# LinefollowerAmateur.net
KiCad netlist of a schematic drawn in EasyEDA
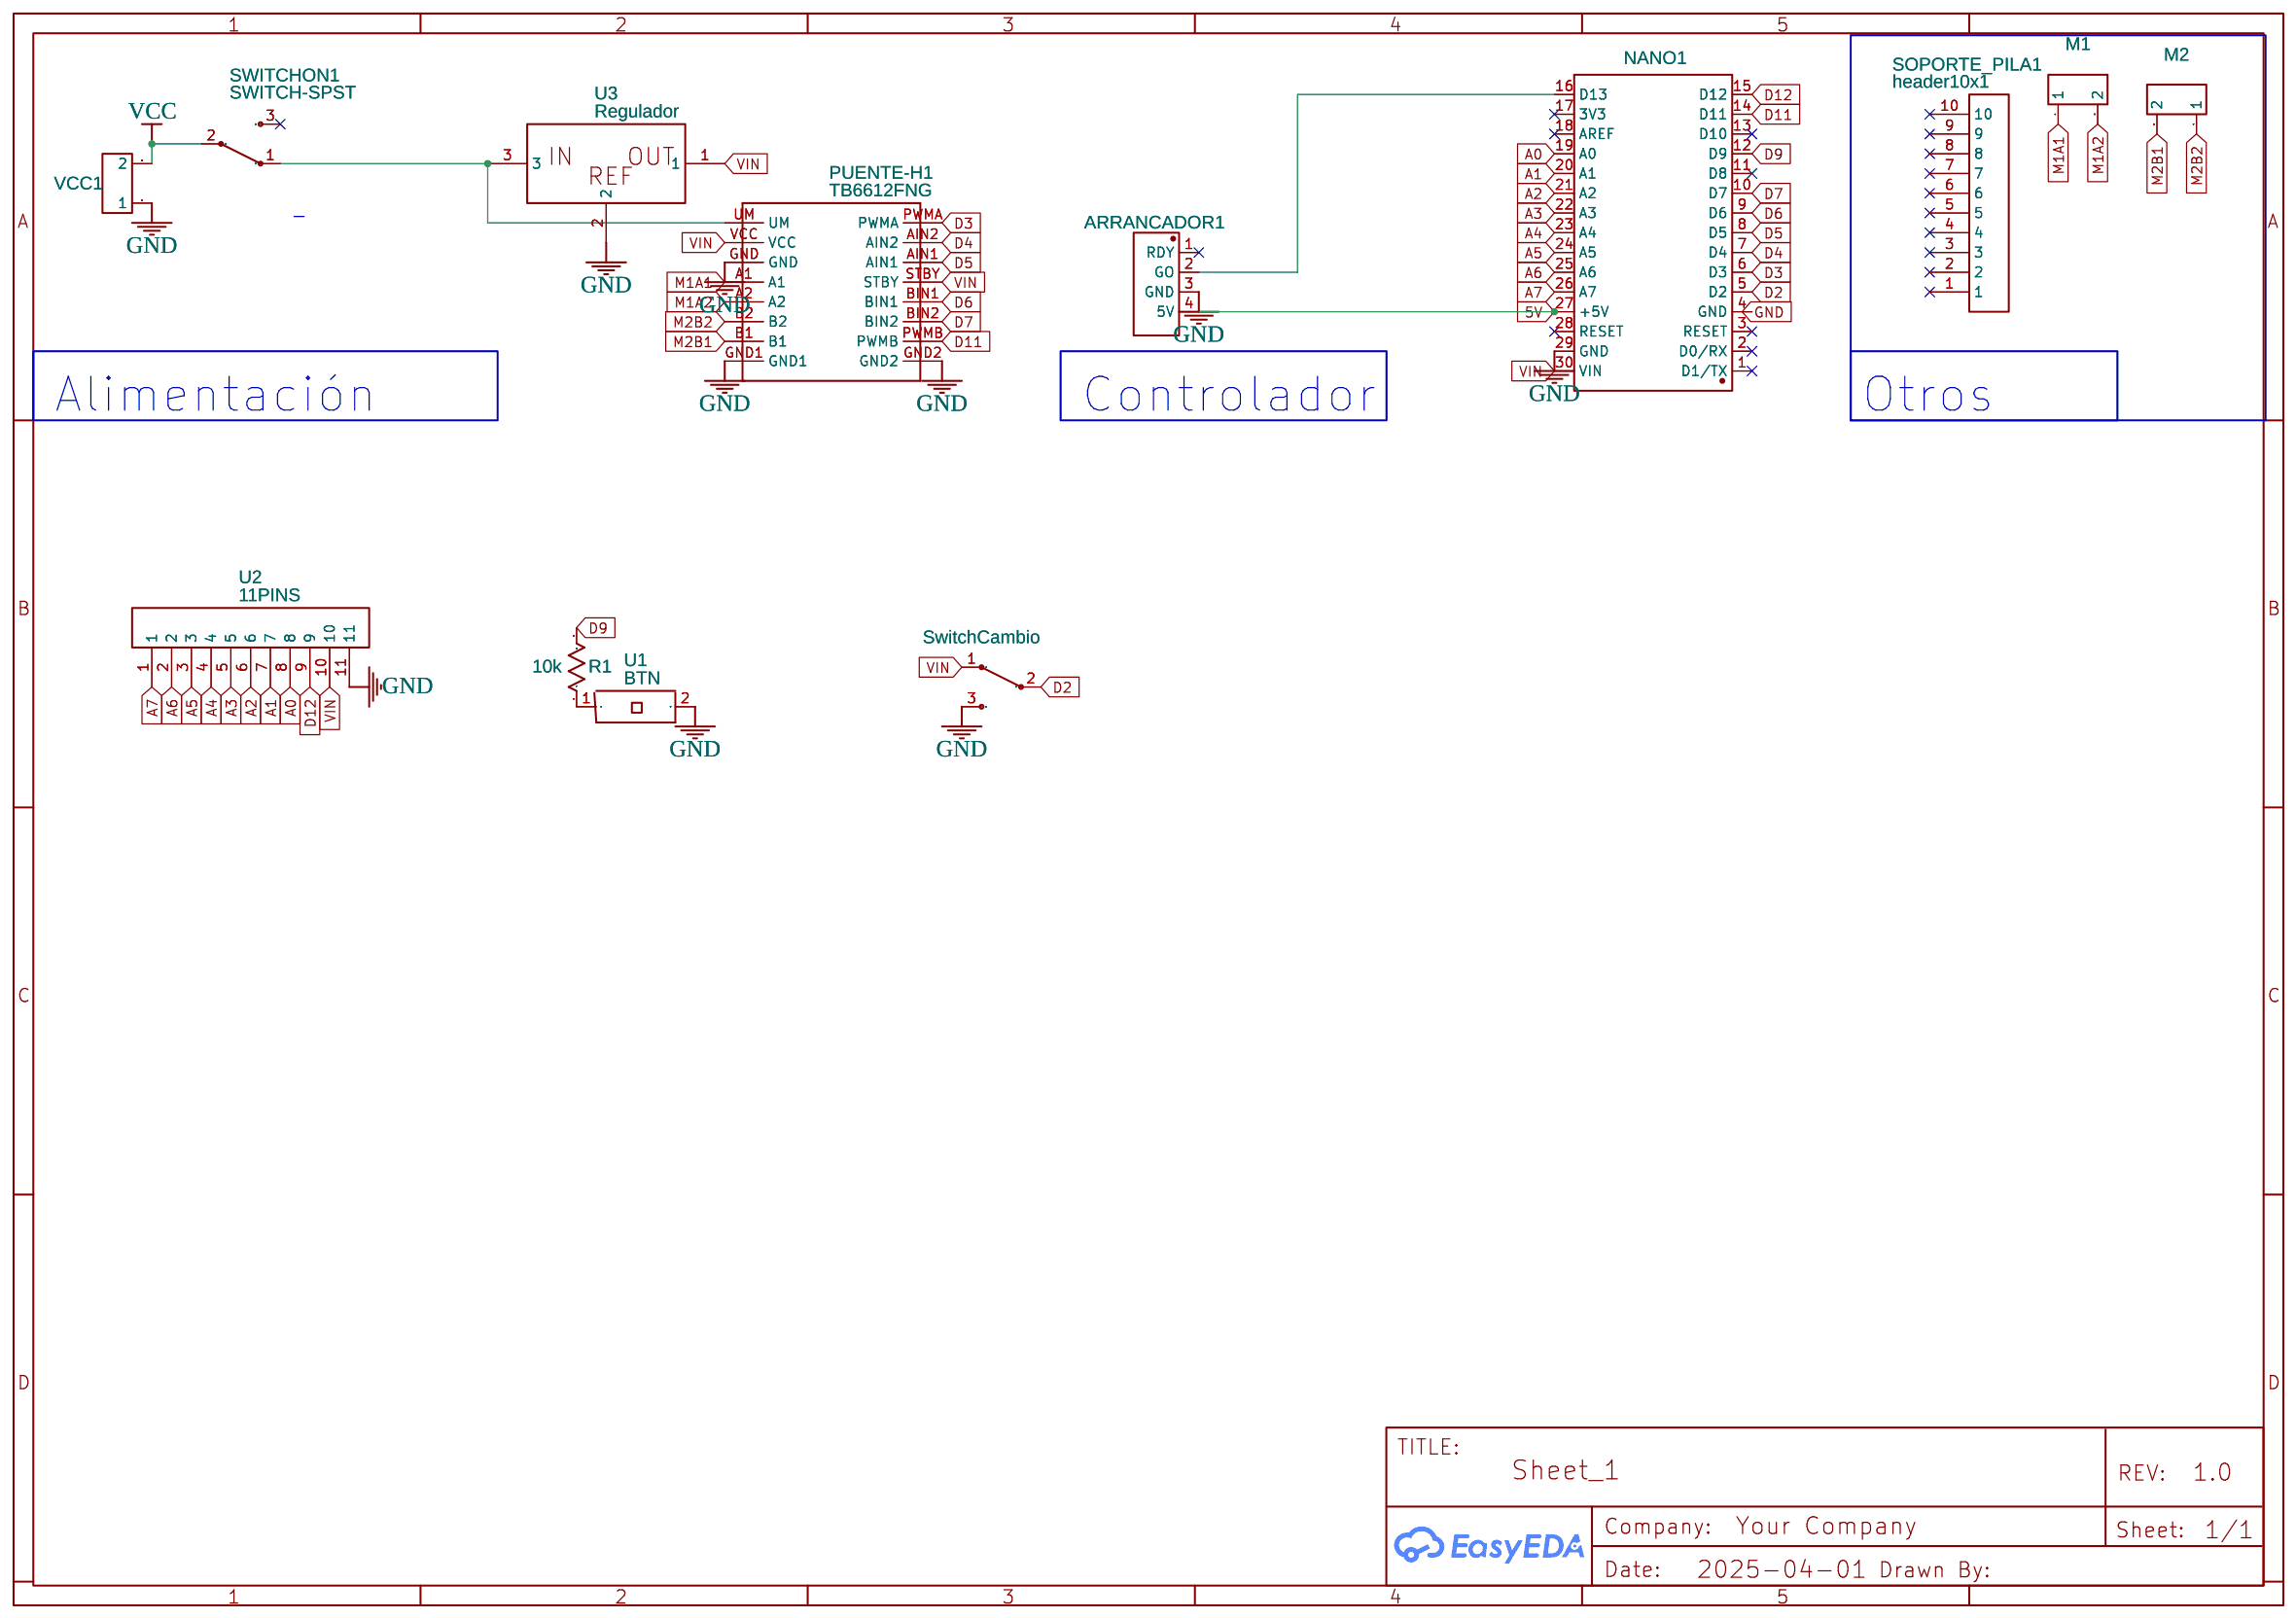
[diagram p0: schematic sheet]

(export (version "E")
  (design (tool "Eeschema 10.0.6"))
  (components
    (comp (ref "ARRANCADOR1") (value "HEADER 1X4P COPY") (libsource (lib "") (part "HEADER 1X4P COPY")))
    (comp (ref "M1")
      (value "CONNECTOR 2 PINS")
      (fields
        (field (name "Manufacturer Part") "Female headerHDR1X8-2.54")
        (field (name "Manufacturer") "BOOMELE")
      )
      (libsource (lib "") (part "HEADER PAD 2X"))
    )
    (comp (ref "M2")
      (value "CONNECTOR 2 PINS")
      (fields
        (field (name "Manufacturer Part") "Female headerHDR1X8-2.54")
        (field (name "Manufacturer") "BOOMELE")
      )
      (libsource (lib "") (part "HEADER PAD 2X_1"))
    )
    (comp (ref "NANO1") (value "ARDUINO_NANO") (libsource (lib "") (part "ARDUINO_NANO")))
    (comp (ref "PUENTE-H1") (value "TB6612FNG") (libsource (lib "") (part "TB6612FNG")))
    (comp (ref "R1")
      (value "10k")
      (fields (field (name "Manufacturer Part") "RESISTOR_ALONG") (field (name "Manufacturer") "MULTICOMP"))
      (libsource (lib "") (part "10k"))
    )
    (comp (ref "SOPORTE_PILA1") (value "header10x1") (libsource (lib "") (part "header10x1")))
    (comp (ref "SWITCHCAMBIO1") (value "SwitchCambio") (libsource (lib "") (part "SWITCH-SPST")))
    (comp (ref "SWITCHON1") (value "SWITCH-SPST") (libsource (lib "") (part "SWITCH-SPST_1")))
    (comp (ref "U1") (value "BTN") (libsource (lib "") (part "BTN")))
    (comp (ref "U2") (value "11PINS") (libsource (lib "") (part "11PINS")))
    (comp (ref "U3") (value "Regulador") (libsource (lib "") (part "Regulador")))
    (comp (ref "VCC1")
      (value "CONNECTOR 2 PINS")
      (fields
        (field (name "Manufacturer Part") "Female headerHDR1X8-2.54")
        (field (name "Manufacturer") "BOOMELE")
      )
      (libsource (lib "") (part "HEADER PAD 2X_2"))
    )
  )
  (nets
    (net (code "1") (name "5V") (class "Default")
      (node (ref "ARRANCADOR1") (pin "4") (pinfunction "5V_4") (pintype "unspecified"))
      (node (ref "NANO1") (pin "27") (pinfunction "+5V_27") (pintype "unspecified"))
    )
    (net (code "2") (name "A0") (class "Default")
      (node (ref "NANO1") (pin "19") (pinfunction "A0_19") (pintype "unspecified"))
      (node (ref "U2") (pin "8") (pinfunction "8_8") (pintype "unspecified"))
    )
    (net (code "3") (name "A1") (class "Default")
      (node (ref "NANO1") (pin "20") (pinfunction "A1_20") (pintype "unspecified"))
      (node (ref "U2") (pin "7") (pinfunction "7_7") (pintype "unspecified"))
    )
    (net (code "4") (name "A2") (class "Default")
      (node (ref "NANO1") (pin "21") (pinfunction "A2_21") (pintype "unspecified"))
      (node (ref "U2") (pin "6") (pinfunction "6_6") (pintype "unspecified"))
    )
    (net (code "5") (name "A3") (class "Default")
      (node (ref "NANO1") (pin "22") (pinfunction "A3_22") (pintype "unspecified"))
      (node (ref "U2") (pin "5") (pinfunction "5_5") (pintype "unspecified"))
    )
    (net (code "6") (name "A4") (class "Default")
      (node (ref "NANO1") (pin "23") (pinfunction "A4_23") (pintype "unspecified"))
      (node (ref "U2") (pin "4") (pinfunction "4_4") (pintype "unspecified"))
    )
    (net (code "7") (name "A5") (class "Default")
      (node (ref "NANO1") (pin "24") (pinfunction "A5_24") (pintype "unspecified"))
      (node (ref "U2") (pin "3") (pinfunction "3_3") (pintype "unspecified"))
    )
    (net (code "8") (name "A6") (class "Default")
      (node (ref "NANO1") (pin "25") (pinfunction "A6_25") (pintype "unspecified"))
      (node (ref "U2") (pin "2") (pinfunction "2_2") (pintype "unspecified"))
    )
    (net (code "9") (name "A7") (class "Default")
      (node (ref "NANO1") (pin "26") (pinfunction "A7_26") (pintype "unspecified"))
      (node (ref "U2") (pin "1") (pinfunction "1_1") (pintype "unspecified"))
    )
    (net (code "10") (name "D2") (class "Default")
      (node (ref "NANO1") (pin "5") (pinfunction "D2_5") (pintype "unspecified"))
      (node (ref "SWITCHCAMBIO1") (pin "2") (pinfunction "2_2") (pintype "unspecified"))
    )
    (net (code "11") (name "D3") (class "Default")
      (node (ref "NANO1") (pin "6") (pinfunction "D3_6") (pintype "unspecified"))
      (node (ref "PUENTE-H1") (pin "PWMA") (pinfunction "PWMA_PWMA") (pintype "bidirectional"))
    )
    (net (code "12") (name "D4") (class "Default")
      (node (ref "NANO1") (pin "7") (pinfunction "D4_7") (pintype "unspecified"))
      (node (ref "PUENTE-H1") (pin "AIN2") (pinfunction "AIN2_AIN2") (pintype "bidirectional"))
    )
    (net (code "13") (name "D5") (class "Default")
      (node (ref "NANO1") (pin "8") (pinfunction "D5_8") (pintype "unspecified"))
      (node (ref "PUENTE-H1") (pin "AIN1") (pinfunction "AIN1_AIN1") (pintype "bidirectional"))
    )
    (net (code "14") (name "D6") (class "Default")
      (node (ref "NANO1") (pin "9") (pinfunction "D6_9") (pintype "unspecified"))
      (node (ref "PUENTE-H1") (pin "BIN1") (pinfunction "BIN1_BIN1") (pintype "bidirectional"))
    )
    (net (code "15") (name "D7") (class "Default")
      (node (ref "NANO1") (pin "10") (pinfunction "D7_10") (pintype "unspecified"))
      (node (ref "PUENTE-H1") (pin "BIN2") (pinfunction "BIN2_BIN2") (pintype "bidirectional"))
    )
    (net (code "16") (name "D9") (class "Default")
      (node (ref "NANO1") (pin "12") (pinfunction "D9_12") (pintype "unspecified"))
      (node (ref "R1") (pin "2") (pinfunction "2_2") (pintype "unspecified"))
    )
    (net (code "17") (name "D11") (class "Default")
      (node (ref "NANO1") (pin "14") (pinfunction "D11_14") (pintype "unspecified"))
      (node (ref "PUENTE-H1") (pin "PWMB") (pinfunction "PWMB_PWMB") (pintype "bidirectional"))
    )
    (net (code "18") (name "D12") (class "Default")
      (node (ref "NANO1") (pin "15") (pinfunction "D12_15") (pintype "unspecified"))
      (node (ref "U2") (pin "9") (pinfunction "9_9") (pintype "unspecified"))
    )
    (net (code "19") (name "GND") (class "Default")
      (node (ref "ARRANCADOR1") (pin "3") (pinfunction "GND_3") (pintype "unspecified"))
      (node (ref "NANO1") (pin "29") (pinfunction "GND_29") (pintype "unspecified"))
      (node (ref "NANO1") (pin "4") (pinfunction "GND_4") (pintype "unspecified"))
      (node (ref "PUENTE-H1") (pin "GND") (pinfunction "GND_GND") (pintype "bidirectional"))
      (node (ref "PUENTE-H1") (pin "GND1") (pinfunction "GND1_GND1") (pintype "bidirectional"))
      (node (ref "PUENTE-H1") (pin "GND2") (pinfunction "GND2_GND2") (pintype "bidirectional"))
      (node (ref "SWITCHCAMBIO1") (pin "3") (pinfunction "3_3") (pintype "unspecified"))
      (node (ref "U1") (pin "2") (pinfunction "2_2") (pintype "unspecified"))
      (node (ref "U2") (pin "11") (pinfunction "11_11") (pintype "unspecified"))
      (node (ref "U3") (pin "2") (pinfunction "2_2") (pintype "unspecified"))
      (node (ref "VCC1") (pin "1") (pinfunction "1_1") (pintype "unspecified"))
    )
    (net (code "20") (name "M1A1") (class "Default")
      (node (ref "M1") (pin "1") (pinfunction "1_1") (pintype "unspecified"))
      (node (ref "PUENTE-H1") (pin "A1") (pinfunction "A1_A1") (pintype "bidirectional"))
    )
    (net (code "21") (name "M1A2") (class "Default")
      (node (ref "M1") (pin "2") (pinfunction "2_2") (pintype "unspecified"))
      (node (ref "PUENTE-H1") (pin "A2") (pinfunction "A2_A2") (pintype "bidirectional"))
    )
    (net (code "22") (name "M2B1") (class "Default")
      (node (ref "M2") (pin "2") (pinfunction "2_2") (pintype "unspecified"))
      (node (ref "PUENTE-H1") (pin "B1") (pinfunction "B1_B1") (pintype "bidirectional"))
    )
    (net (code "23") (name "M2B2") (class "Default")
      (node (ref "M2") (pin "1") (pinfunction "1_1") (pintype "unspecified"))
      (node (ref "PUENTE-H1") (pin "B2") (pinfunction "B2_B2") (pintype "bidirectional"))
    )
    (net (code "24") (name "Net-(ARRANCADOR1-GO)") (class "Default")
      (node (ref "ARRANCADOR1") (pin "2") (pinfunction "GO_2") (pintype "unspecified"))
      (node (ref "NANO1") (pin "16") (pinfunction "D13_16") (pintype "unspecified"))
    )
    (net (code "25") (name "Net-(PUENTE-H1-PadUM)") (class "Default")
      (node (ref "PUENTE-H1") (pin "UM") (pinfunction "UM_UM") (pintype "bidirectional"))
      (node (ref "SWITCHON1") (pin "1") (pinfunction "1_1") (pintype "unspecified"))
      (node (ref "U3") (pin "3") (pinfunction "3_3") (pintype "unspecified"))
    )
    (net (code "26") (name "Net-(R1-Pad1)") (class "Default")
      (node (ref "R1") (pin "1") (pinfunction "1_1") (pintype "unspecified"))
      (node (ref "U1") (pin "1") (pinfunction "1_1") (pintype "unspecified"))
    )
    (net (code "27") (name "VCC") (class "Default")
      (node (ref "SWITCHON1") (pin "2") (pinfunction "2_2") (pintype "unspecified"))
      (node (ref "VCC1") (pin "2") (pinfunction "2_2") (pintype "unspecified"))
    )
    (net (code "28") (name "VIN") (class "Default")
      (node (ref "NANO1") (pin "30") (pinfunction "VIN_30") (pintype "unspecified"))
      (node (ref "PUENTE-H1") (pin "STBY") (pinfunction "STBY_STBY") (pintype "bidirectional"))
      (node (ref "PUENTE-H1") (pin "VCC") (pinfunction "VCC_VCC") (pintype "bidirectional"))
      (node (ref "SWITCHCAMBIO1") (pin "1") (pinfunction "1_1") (pintype "unspecified"))
      (node (ref "U2") (pin "10") (pinfunction "10_10") (pintype "unspecified"))
      (node (ref "U3") (pin "1") (pinfunction "1_1") (pintype "unspecified"))
    )
    (net (code "29") (name "unconnected-(ARRANCADOR1-RDY-Pad1)") (class "Default")
      (node (ref "ARRANCADOR1") (pin "1") (pinfunction "RDY_1") (pintype "unspecified+no_connect"))
    )
    (net (code "30") (name "unconnected-(NANO1-3V3-Pad17)") (class "Default")
      (node (ref "NANO1") (pin "17") (pinfunction "3V3_17") (pintype "unspecified+no_connect"))
    )
    (net (code "31") (name "unconnected-(NANO1-AREF-Pad18)") (class "Default")
      (node (ref "NANO1") (pin "18") (pinfunction "AREF_18") (pintype "unspecified+no_connect"))
    )
    (net (code "32") (name "unconnected-(NANO1-D0{slash}RX-Pad2)") (class "Default")
      (node (ref "NANO1") (pin "2") (pinfunction "D0/RX_2") (pintype "unspecified+no_connect"))
    )
    (net (code "33") (name "unconnected-(NANO1-D1{slash}TX-Pad1)") (class "Default")
      (node (ref "NANO1") (pin "1") (pinfunction "D1/TX_1") (pintype "unspecified+no_connect"))
    )
    (net (code "34") (name "unconnected-(NANO1-D8-Pad11)") (class "Default")
      (node (ref "NANO1") (pin "11") (pinfunction "D8_11") (pintype "unspecified+no_connect"))
    )
    (net (code "35") (name "unconnected-(NANO1-D10-Pad13)") (class "Default")
      (node (ref "NANO1") (pin "13") (pinfunction "D10_13") (pintype "unspecified+no_connect"))
    )
    (net (code "36") (name "unconnected-(NANO1-RESET-Pad3)") (class "Default")
      (node (ref "NANO1") (pin "3") (pinfunction "RESET_3") (pintype "unspecified+no_connect"))
    )
    (net (code "37") (name "unconnected-(NANO1-RESET-Pad28)") (class "Default")
      (node (ref "NANO1") (pin "28") (pinfunction "RESET_28") (pintype "unspecified+no_connect"))
    )
    (net (code "38") (name "unconnected-(SOPORTE_PILA1-Pad1)") (class "Default")
      (node (ref "SOPORTE_PILA1") (pin "1") (pinfunction "1_1") (pintype "unspecified+no_connect"))
    )
    (net (code "39") (name "unconnected-(SOPORTE_PILA1-Pad2)") (class "Default")
      (node (ref "SOPORTE_PILA1") (pin "2") (pinfunction "2_2") (pintype "unspecified+no_connect"))
    )
    (net (code "40") (name "unconnected-(SOPORTE_PILA1-Pad3)") (class "Default")
      (node (ref "SOPORTE_PILA1") (pin "3") (pinfunction "3_3") (pintype "unspecified+no_connect"))
    )
    (net (code "41") (name "unconnected-(SOPORTE_PILA1-Pad4)") (class "Default")
      (node (ref "SOPORTE_PILA1") (pin "4") (pinfunction "4_4") (pintype "unspecified+no_connect"))
    )
    (net (code "42") (name "unconnected-(SOPORTE_PILA1-Pad5)") (class "Default")
      (node (ref "SOPORTE_PILA1") (pin "5") (pinfunction "5_5") (pintype "unspecified+no_connect"))
    )
    (net (code "43") (name "unconnected-(SOPORTE_PILA1-Pad6)") (class "Default")
      (node (ref "SOPORTE_PILA1") (pin "6") (pinfunction "6_6") (pintype "unspecified+no_connect"))
    )
    (net (code "44") (name "unconnected-(SOPORTE_PILA1-Pad7)") (class "Default")
      (node (ref "SOPORTE_PILA1") (pin "7") (pinfunction "7_7") (pintype "unspecified+no_connect"))
    )
    (net (code "45") (name "unconnected-(SOPORTE_PILA1-Pad8)") (class "Default")
      (node (ref "SOPORTE_PILA1") (pin "8") (pinfunction "8_8") (pintype "unspecified+no_connect"))
    )
    (net (code "46") (name "unconnected-(SOPORTE_PILA1-Pad9)") (class "Default")
      (node (ref "SOPORTE_PILA1") (pin "9") (pinfunction "9_9") (pintype "unspecified+no_connect"))
    )
    (net (code "47") (name "unconnected-(SOPORTE_PILA1-Pad10)") (class "Default")
      (node (ref "SOPORTE_PILA1") (pin "10") (pinfunction "10_10") (pintype "unspecified+no_connect"))
    )
    (net (code "48") (name "unconnected-(SWITCHON1-Pad3)") (class "Default")
      (node (ref "SWITCHON1") (pin "3") (pinfunction "3_3") (pintype "unspecified+no_connect"))
    )
  )
)
